# Microcontroller.net
KiCad netlist of a schematic drawn in Altium Designer
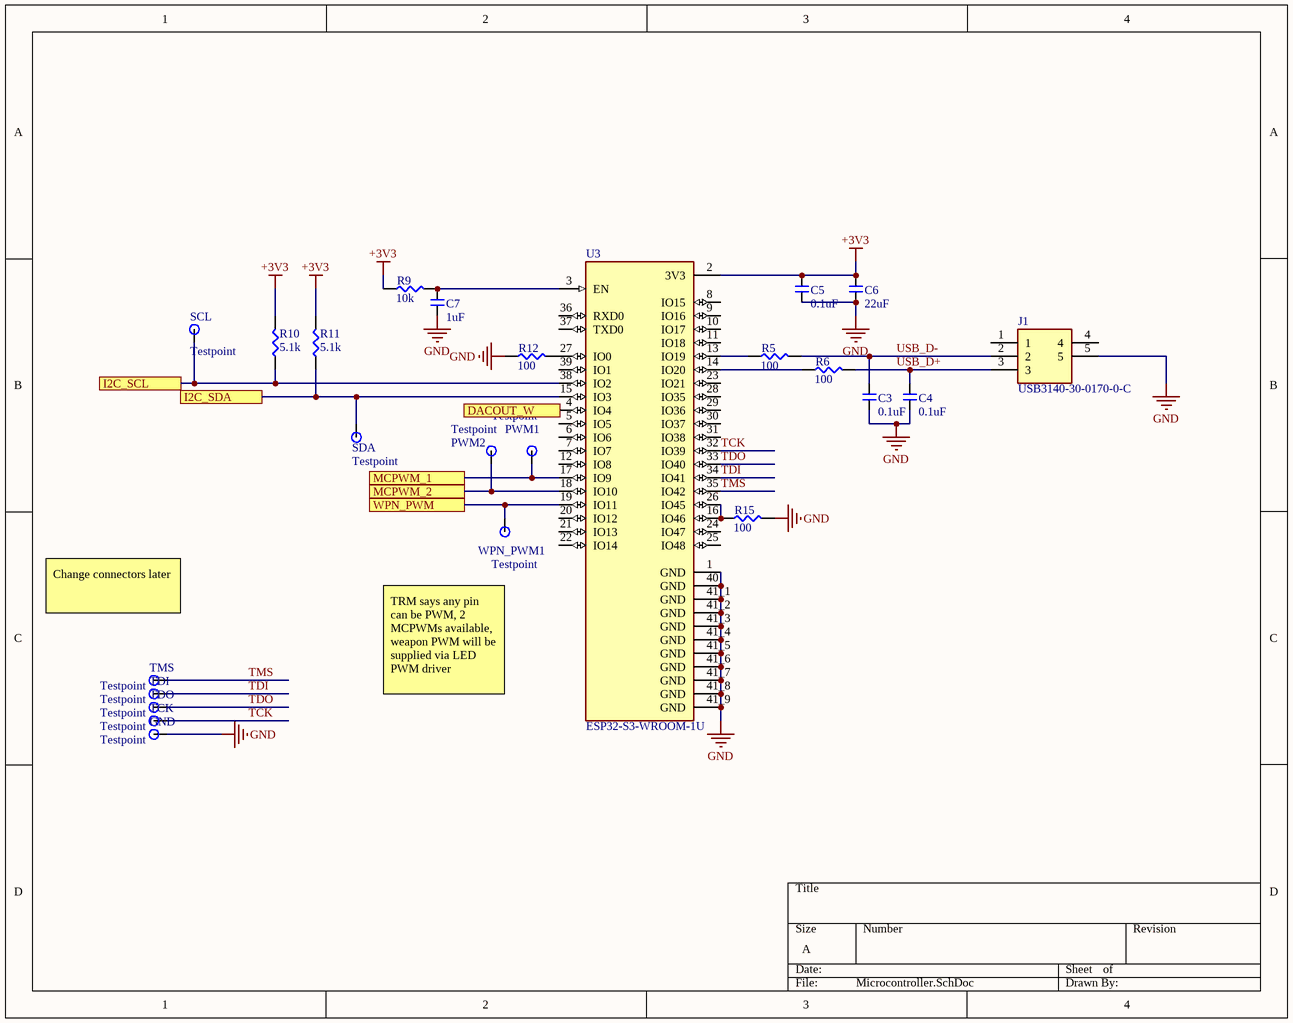
[diagram p0: Microcontroller.SchDoc]

(export (version "E")
  (design (tool "Eeschema 10.0.6"))
  (components
    (comp (ref "C3")
      (value "0.1uF")
      (footprint "CAP-0603")
      (fields (field (name "SOURCE") "ife19_Elec_Library.SchLib"))
      (libsource (lib "Illini Formula Electric") (part "CAP-0603"))
    )
    (comp (ref "C4")
      (value "0.1uF")
      (footprint "CAP-0603")
      (fields (field (name "SOURCE") "ife19_Elec_Library.SchLib"))
      (libsource (lib "Illini Formula Electric") (part "CAP-0603"))
    )
    (comp (ref "C5")
      (value "0.1uF")
      (footprint "CAP-0603")
      (fields (field (name "SOURCE") "ife19_Elec_Library.SchLib"))
      (libsource (lib "Illini Formula Electric") (part "CAP-0603"))
    )
    (comp (ref "C6")
      (value "22uF")
      (footprint "CAP-0603")
      (fields (field (name "SOURCE") "ife19_Elec_Library.SchLib"))
      (libsource (lib "Illini Formula Electric") (part "CAP-0603"))
    )
    (comp (ref "C7")
      (value "1uF")
      (footprint "CAP-0603")
      (fields (field (name "SOURCE") "ife19_Elec_Library.SchLib"))
      (libsource (lib "Illini Formula Electric") (part "CAP-0603"))
    )
    (comp (ref "GND")
      (value "Testpoint")
      (footprint "Testpoint")
      (fields (field (name "SOURCE") "ife19_Elec_Library.SchLib"))
      (libsource (lib "Illini Formula Electric") (part "Testpoint"))
    )
    (comp (ref "J1")
      (value "USB3140-30-0170-0-C")
      (footprint "SamacSys:USB31403001700C")
      (description "Connector")
      (fields (field (name "MOUSER PART NUMBER") "640-USB31403001700C"))
      (libsource (lib "*") (part "USB3140-30-0170-0-C"))
    )
    (comp (ref "PWM1")
      (value "Testpoint")
      (footprint "Testpoint")
      (fields (field (name "SOURCE") "ife19_Elec_Library.SchLib"))
      (libsource (lib "Illini Formula Electric") (part "Testpoint"))
    )
    (comp (ref "PWM2")
      (value "Testpoint")
      (footprint "Testpoint")
      (fields (field (name "SOURCE") "ife19_Elec_Library.SchLib"))
      (libsource (lib "Illini Formula Electric") (part "Testpoint"))
    )
    (comp (ref "R5")
      (value "100")
      (footprint "RES-0603")
      (fields (field (name "SOURCE") "ife19_Elec_Library.SchLib"))
      (libsource (lib "Illini Formula Electric") (part "Symbol"))
    )
    (comp (ref "R6")
      (value "100")
      (footprint "RES-0603")
      (fields (field (name "SOURCE") "ife19_Elec_Library.SchLib"))
      (libsource (lib "Illini Formula Electric") (part "Symbol"))
    )
    (comp (ref "R9")
      (value "10k")
      (footprint "RES-0603")
      (fields (field (name "SOURCE") "ife19_Elec_Library.SchLib"))
      (libsource (lib "Illini Formula Electric") (part "Symbol"))
    )
    (comp (ref "R10")
      (value "5.1k")
      (footprint "RES-0603")
      (fields (field (name "SOURCE") "ife19_Elec_Library.SchLib"))
      (libsource (lib "Illini Formula Electric") (part "Symbol"))
    )
    (comp (ref "R11")
      (value "5.1k")
      (footprint "RES-0603")
      (fields (field (name "SOURCE") "ife19_Elec_Library.SchLib"))
      (libsource (lib "Illini Formula Electric") (part "Symbol"))
    )
    (comp (ref "R12")
      (value "100")
      (footprint "RES-0603")
      (fields (field (name "SOURCE") "ife19_Elec_Library.SchLib"))
      (libsource (lib "Illini Formula Electric") (part "Symbol"))
    )
    (comp (ref "R15")
      (value "100")
      (footprint "RES-0603")
      (fields (field (name "SOURCE") "ife19_Elec_Library.SchLib"))
      (libsource (lib "Illini Formula Electric") (part "Symbol"))
    )
    (comp (ref "SCL")
      (value "Testpoint")
      (footprint "Testpoint")
      (fields (field (name "SOURCE") "ife19_Elec_Library.SchLib"))
      (libsource (lib "Illini Formula Electric") (part "Testpoint"))
    )
    (comp (ref "SDA")
      (value "Testpoint")
      (footprint "Testpoint")
      (fields (field (name "SOURCE") "ife19_Elec_Library.SchLib"))
      (libsource (lib "Illini Formula Electric") (part "Testpoint"))
    )
    (comp (ref "TCK")
      (value "Testpoint")
      (footprint "Testpoint")
      (fields (field (name "SOURCE") "ife19_Elec_Library.SchLib"))
      (libsource (lib "Illini Formula Electric") (part "Testpoint"))
    )
    (comp (ref "TDI")
      (value "Testpoint")
      (footprint "Testpoint")
      (fields (field (name "SOURCE") "ife19_Elec_Library.SchLib"))
      (libsource (lib "Illini Formula Electric") (part "Testpoint"))
    )
    (comp (ref "TDO")
      (value "Testpoint")
      (footprint "Testpoint")
      (fields (field (name "SOURCE") "ife19_Elec_Library.SchLib"))
      (libsource (lib "Illini Formula Electric") (part "Testpoint"))
    )
    (comp (ref "TMS")
      (value "Testpoint")
      (footprint "Testpoint")
      (fields (field (name "SOURCE") "ife19_Elec_Library.SchLib"))
      (libsource (lib "Illini Formula Electric") (part "Testpoint"))
    )
    (comp (ref "U3")
      (value "ESP32-S3-WROOM-1U")
      (footprint "XCVR_ESP32-S3-WROOM-1U")
      (description "2.4 GHz Wi-Fi (802.11 b/g/n) and Bluetooth 5 (LE) module")
      (fields (field (name "MF") "Espressif Systems"))
      (libsource (lib "Illini Formula Electric") (part "ESP32-S3-WROOM-1U"))
    )
    (comp (ref "WPN_PWM1")
      (value "Testpoint")
      (footprint "Testpoint")
      (fields (field (name "SOURCE") "ife19_Elec_Library.SchLib"))
      (libsource (lib "Illini Formula Electric") (part "Testpoint"))
    )
  )
  (nets
    (net (code "1") (name "+3V3") (class "Default")
      (node (ref "C5") (pin "2") (pinfunction "2_2") (pintype "passive"))
      (node (ref "C6") (pin "2") (pinfunction "2_2") (pintype "passive"))
      (node (ref "R10") (pin "2") (pinfunction "2_2") (pintype "passive"))
      (node (ref "R11") (pin "2") (pinfunction "2_2") (pintype "passive"))
      (node (ref "R9") (pin "1") (pinfunction "1_1") (pintype "passive"))
      (node (ref "U3") (pin "2") (pinfunction "3V3_2") (pintype "power_in"))
    )
    (net (code "3") (name "/I2C_SCL") (class "Default")
      (node (ref "R10") (pin "1") (pinfunction "1_1") (pintype "passive"))
      (node (ref "SCL") (pin "1") (pinfunction "1_1") (pintype "passive"))
      (node (ref "U3") (pin "38") (pinfunction "IO2_38") (pintype "bidirectional"))
    )
    (net (code "4") (name "/I2C_SDA") (class "Default")
      (node (ref "R11") (pin "1") (pinfunction "1_1") (pintype "passive"))
      (node (ref "SDA") (pin "1") (pinfunction "1_1") (pintype "passive"))
      (node (ref "U3") (pin "15") (pinfunction "IO3_15") (pintype "bidirectional"))
    )
    (net (code "5") (name "/MCPWM_1") (class "Default")
      (node (ref "PWM1") (pin "1") (pinfunction "1_1") (pintype "passive"))
      (node (ref "U3") (pin "17") (pinfunction "IO9_17") (pintype "bidirectional"))
    )
    (net (code "6") (name "/MCPWM_2") (class "Default")
      (node (ref "PWM2") (pin "1") (pinfunction "1_1") (pintype "passive"))
      (node (ref "U3") (pin "18") (pinfunction "IO10_18") (pintype "bidirectional"))
    )
    (net (code "7") (name "/TCK") (class "Default")
      (node (ref "TCK") (pin "1") (pinfunction "1_1") (pintype "passive"))
      (node (ref "U3") (pin "32") (pinfunction "IO39_32") (pintype "bidirectional"))
    )
    (net (code "8") (name "/TDI") (class "Default")
      (node (ref "TDI") (pin "1") (pinfunction "1_1") (pintype "passive"))
      (node (ref "U3") (pin "34") (pinfunction "IO41_34") (pintype "bidirectional"))
    )
    (net (code "9") (name "/TDO") (class "Default")
      (node (ref "TDO") (pin "1") (pinfunction "1_1") (pintype "passive"))
      (node (ref "U3") (pin "33") (pinfunction "IO40_33") (pintype "bidirectional"))
    )
    (net (code "10") (name "/TMS") (class "Default")
      (node (ref "TMS") (pin "1") (pinfunction "1_1") (pintype "passive"))
      (node (ref "U3") (pin "35") (pinfunction "IO42_35") (pintype "bidirectional"))
    )
    (net (code "11") (name "/USB_D+") (class "Default")
      (node (ref "C4") (pin "2") (pinfunction "2_2") (pintype "passive"))
      (node (ref "J1") (pin "3") (pinfunction "3_3") (pintype "passive"))
      (node (ref "R6") (pin "2") (pinfunction "2_2") (pintype "passive"))
    )
    (net (code "12") (name "/USB_D-") (class "Default")
      (node (ref "C3") (pin "2") (pinfunction "2_2") (pintype "passive"))
      (node (ref "J1") (pin "2") (pinfunction "2_2") (pintype "passive"))
      (node (ref "R5") (pin "2") (pinfunction "2_2") (pintype "passive"))
    )
    (net (code "13") (name "/WPN_PWM") (class "Default")
      (node (ref "U3") (pin "19") (pinfunction "IO11_19") (pintype "bidirectional"))
      (node (ref "WPN_PWM1") (pin "1") (pinfunction "1_1") (pintype "passive"))
    )
    (net (code "14") (name "GND") (class "Default")
      (node (ref "C3") (pin "1") (pinfunction "1_1") (pintype "passive"))
      (node (ref "C4") (pin "1") (pinfunction "1_1") (pintype "passive"))
      (node (ref "C5") (pin "1") (pinfunction "1_1") (pintype "passive"))
      (node (ref "C6") (pin "1") (pinfunction "1_1") (pintype "passive"))
      (node (ref "C7") (pin "1") (pinfunction "1_1") (pintype "passive"))
      (node (ref "GND") (pin "1") (pinfunction "1_1") (pintype "passive"))
      (node (ref "J1") (pin "5") (pinfunction "5_5") (pintype "passive"))
      (node (ref "R12") (pin "1") (pinfunction "1_1") (pintype "passive"))
      (node (ref "R15") (pin "2") (pinfunction "2_2") (pintype "passive"))
      (node (ref "U3") (pin "1") (pinfunction "GND_1") (pintype "power_in"))
      (node (ref "U3") (pin "40") (pinfunction "GND_40") (pintype "power_in"))
      (node (ref "U3") (pin "41_1") (pinfunction "GND_41_1") (pintype "power_in"))
      (node (ref "U3") (pin "41_2") (pinfunction "GND_41_2") (pintype "power_in"))
      (node (ref "U3") (pin "41_3") (pinfunction "GND_41_3") (pintype "power_in"))
      (node (ref "U3") (pin "41_4") (pinfunction "GND_41_4") (pintype "power_in"))
      (node (ref "U3") (pin "41_5") (pinfunction "GND_41_5") (pintype "power_in"))
      (node (ref "U3") (pin "41_6") (pinfunction "GND_41_6") (pintype "power_in"))
      (node (ref "U3") (pin "41_7") (pinfunction "GND_41_7") (pintype "power_in"))
      (node (ref "U3") (pin "41_8") (pinfunction "GND_41_8") (pintype "power_in"))
      (node (ref "U3") (pin "41_9") (pinfunction "GND_41_9") (pintype "power_in"))
    )
    (net (code "15") (name "Net-(U3-EN)") (class "Default")
      (node (ref "C7") (pin "2") (pinfunction "2_2") (pintype "passive"))
      (node (ref "R9") (pin "2") (pinfunction "2_2") (pintype "passive"))
      (node (ref "U3") (pin "3") (pinfunction "EN_3") (pintype "input"))
    )
    (net (code "16") (name "Net-(U3-IO0)") (class "Default")
      (node (ref "R12") (pin "2") (pinfunction "2_2") (pintype "passive"))
      (node (ref "U3") (pin "27") (pinfunction "IO0_27") (pintype "bidirectional"))
    )
    (net (code "17") (name "Net-(U3-IO19)") (class "Default")
      (node (ref "R5") (pin "1") (pinfunction "1_1") (pintype "passive"))
      (node (ref "U3") (pin "13") (pinfunction "IO19_13") (pintype "bidirectional"))
    )
    (net (code "18") (name "Net-(U3-IO20)") (class "Default")
      (node (ref "R6") (pin "1") (pinfunction "1_1") (pintype "passive"))
      (node (ref "U3") (pin "14") (pinfunction "IO20_14") (pintype "bidirectional"))
    )
    (net (code "19") (name "Net-(U3-IO45)") (class "Default")
      (node (ref "R15") (pin "1") (pinfunction "1_1") (pintype "passive"))
      (node (ref "U3") (pin "16") (pinfunction "IO46_16") (pintype "bidirectional"))
      (node (ref "U3") (pin "26") (pinfunction "IO45_26") (pintype "bidirectional"))
    )
    (net (code "20") (name "unconnected-(J1-Pad1)") (class "Default")
      (node (ref "J1") (pin "1") (pinfunction "1_1") (pintype "passive"))
    )
    (net (code "21") (name "unconnected-(J1-Pad4)") (class "Default")
      (node (ref "J1") (pin "4") (pinfunction "4_4") (pintype "passive"))
    )
    (net (code "22") (name "unconnected-(U3-IO1-Pad39)") (class "Default")
      (node (ref "U3") (pin "39") (pinfunction "IO1_39") (pintype "bidirectional"))
    )
    (net (code "23") (name "unconnected-(U3-IO4-Pad4)") (class "Default")
      (node (ref "U3") (pin "4") (pinfunction "IO4_4") (pintype "bidirectional"))
    )
    (net (code "24") (name "unconnected-(U3-IO5-Pad5)") (class "Default")
      (node (ref "U3") (pin "5") (pinfunction "IO5_5") (pintype "bidirectional"))
    )
    (net (code "25") (name "unconnected-(U3-IO6-Pad6)") (class "Default")
      (node (ref "U3") (pin "6") (pinfunction "IO6_6") (pintype "bidirectional"))
    )
    (net (code "26") (name "unconnected-(U3-IO7-Pad7)") (class "Default")
      (node (ref "U3") (pin "7") (pinfunction "IO7_7") (pintype "bidirectional"))
    )
    (net (code "27") (name "unconnected-(U3-IO8-Pad12)") (class "Default")
      (node (ref "U3") (pin "12") (pinfunction "IO8_12") (pintype "bidirectional"))
    )
    (net (code "28") (name "unconnected-(U3-IO12-Pad20)") (class "Default")
      (node (ref "U3") (pin "20") (pinfunction "IO12_20") (pintype "bidirectional"))
    )
    (net (code "29") (name "unconnected-(U3-IO13-Pad21)") (class "Default")
      (node (ref "U3") (pin "21") (pinfunction "IO13_21") (pintype "bidirectional"))
    )
    (net (code "30") (name "unconnected-(U3-IO14-Pad22)") (class "Default")
      (node (ref "U3") (pin "22") (pinfunction "IO14_22") (pintype "bidirectional"))
    )
    (net (code "31") (name "unconnected-(U3-IO15-Pad8)") (class "Default")
      (node (ref "U3") (pin "8") (pinfunction "IO15_8") (pintype "bidirectional"))
    )
    (net (code "32") (name "unconnected-(U3-IO16-Pad9)") (class "Default")
      (node (ref "U3") (pin "9") (pinfunction "IO16_9") (pintype "bidirectional"))
    )
    (net (code "33") (name "unconnected-(U3-IO17-Pad10)") (class "Default")
      (node (ref "U3") (pin "10") (pinfunction "IO17_10") (pintype "bidirectional"))
    )
    (net (code "34") (name "unconnected-(U3-IO18-Pad11)") (class "Default")
      (node (ref "U3") (pin "11") (pinfunction "IO18_11") (pintype "bidirectional"))
    )
    (net (code "35") (name "unconnected-(U3-IO21-Pad23)") (class "Default")
      (node (ref "U3") (pin "23") (pinfunction "IO21_23") (pintype "bidirectional"))
    )
    (net (code "36") (name "unconnected-(U3-IO35-Pad28)") (class "Default")
      (node (ref "U3") (pin "28") (pinfunction "IO35_28") (pintype "bidirectional"))
    )
    (net (code "37") (name "unconnected-(U3-IO36-Pad29)") (class "Default")
      (node (ref "U3") (pin "29") (pinfunction "IO36_29") (pintype "bidirectional"))
    )
    (net (code "38") (name "unconnected-(U3-IO37-Pad30)") (class "Default")
      (node (ref "U3") (pin "30") (pinfunction "IO37_30") (pintype "bidirectional"))
    )
    (net (code "39") (name "unconnected-(U3-IO38-Pad31)") (class "Default")
      (node (ref "U3") (pin "31") (pinfunction "IO38_31") (pintype "bidirectional"))
    )
    (net (code "40") (name "unconnected-(U3-IO47-Pad24)") (class "Default")
      (node (ref "U3") (pin "24") (pinfunction "IO47_24") (pintype "bidirectional"))
    )
    (net (code "41") (name "unconnected-(U3-IO48-Pad25)") (class "Default")
      (node (ref "U3") (pin "25") (pinfunction "IO48_25") (pintype "bidirectional"))
    )
    (net (code "42") (name "unconnected-(U3-RXD0-Pad36)") (class "Default")
      (node (ref "U3") (pin "36") (pinfunction "RXD0_36") (pintype "bidirectional"))
    )
    (net (code "43") (name "unconnected-(U3-TXD0-Pad37)") (class "Default")
      (node (ref "U3") (pin "37") (pinfunction "TXD0_37") (pintype "bidirectional"))
    )
  )
)
